# untitled.net
KiCad netlist of a schematic drawn in EAGLE
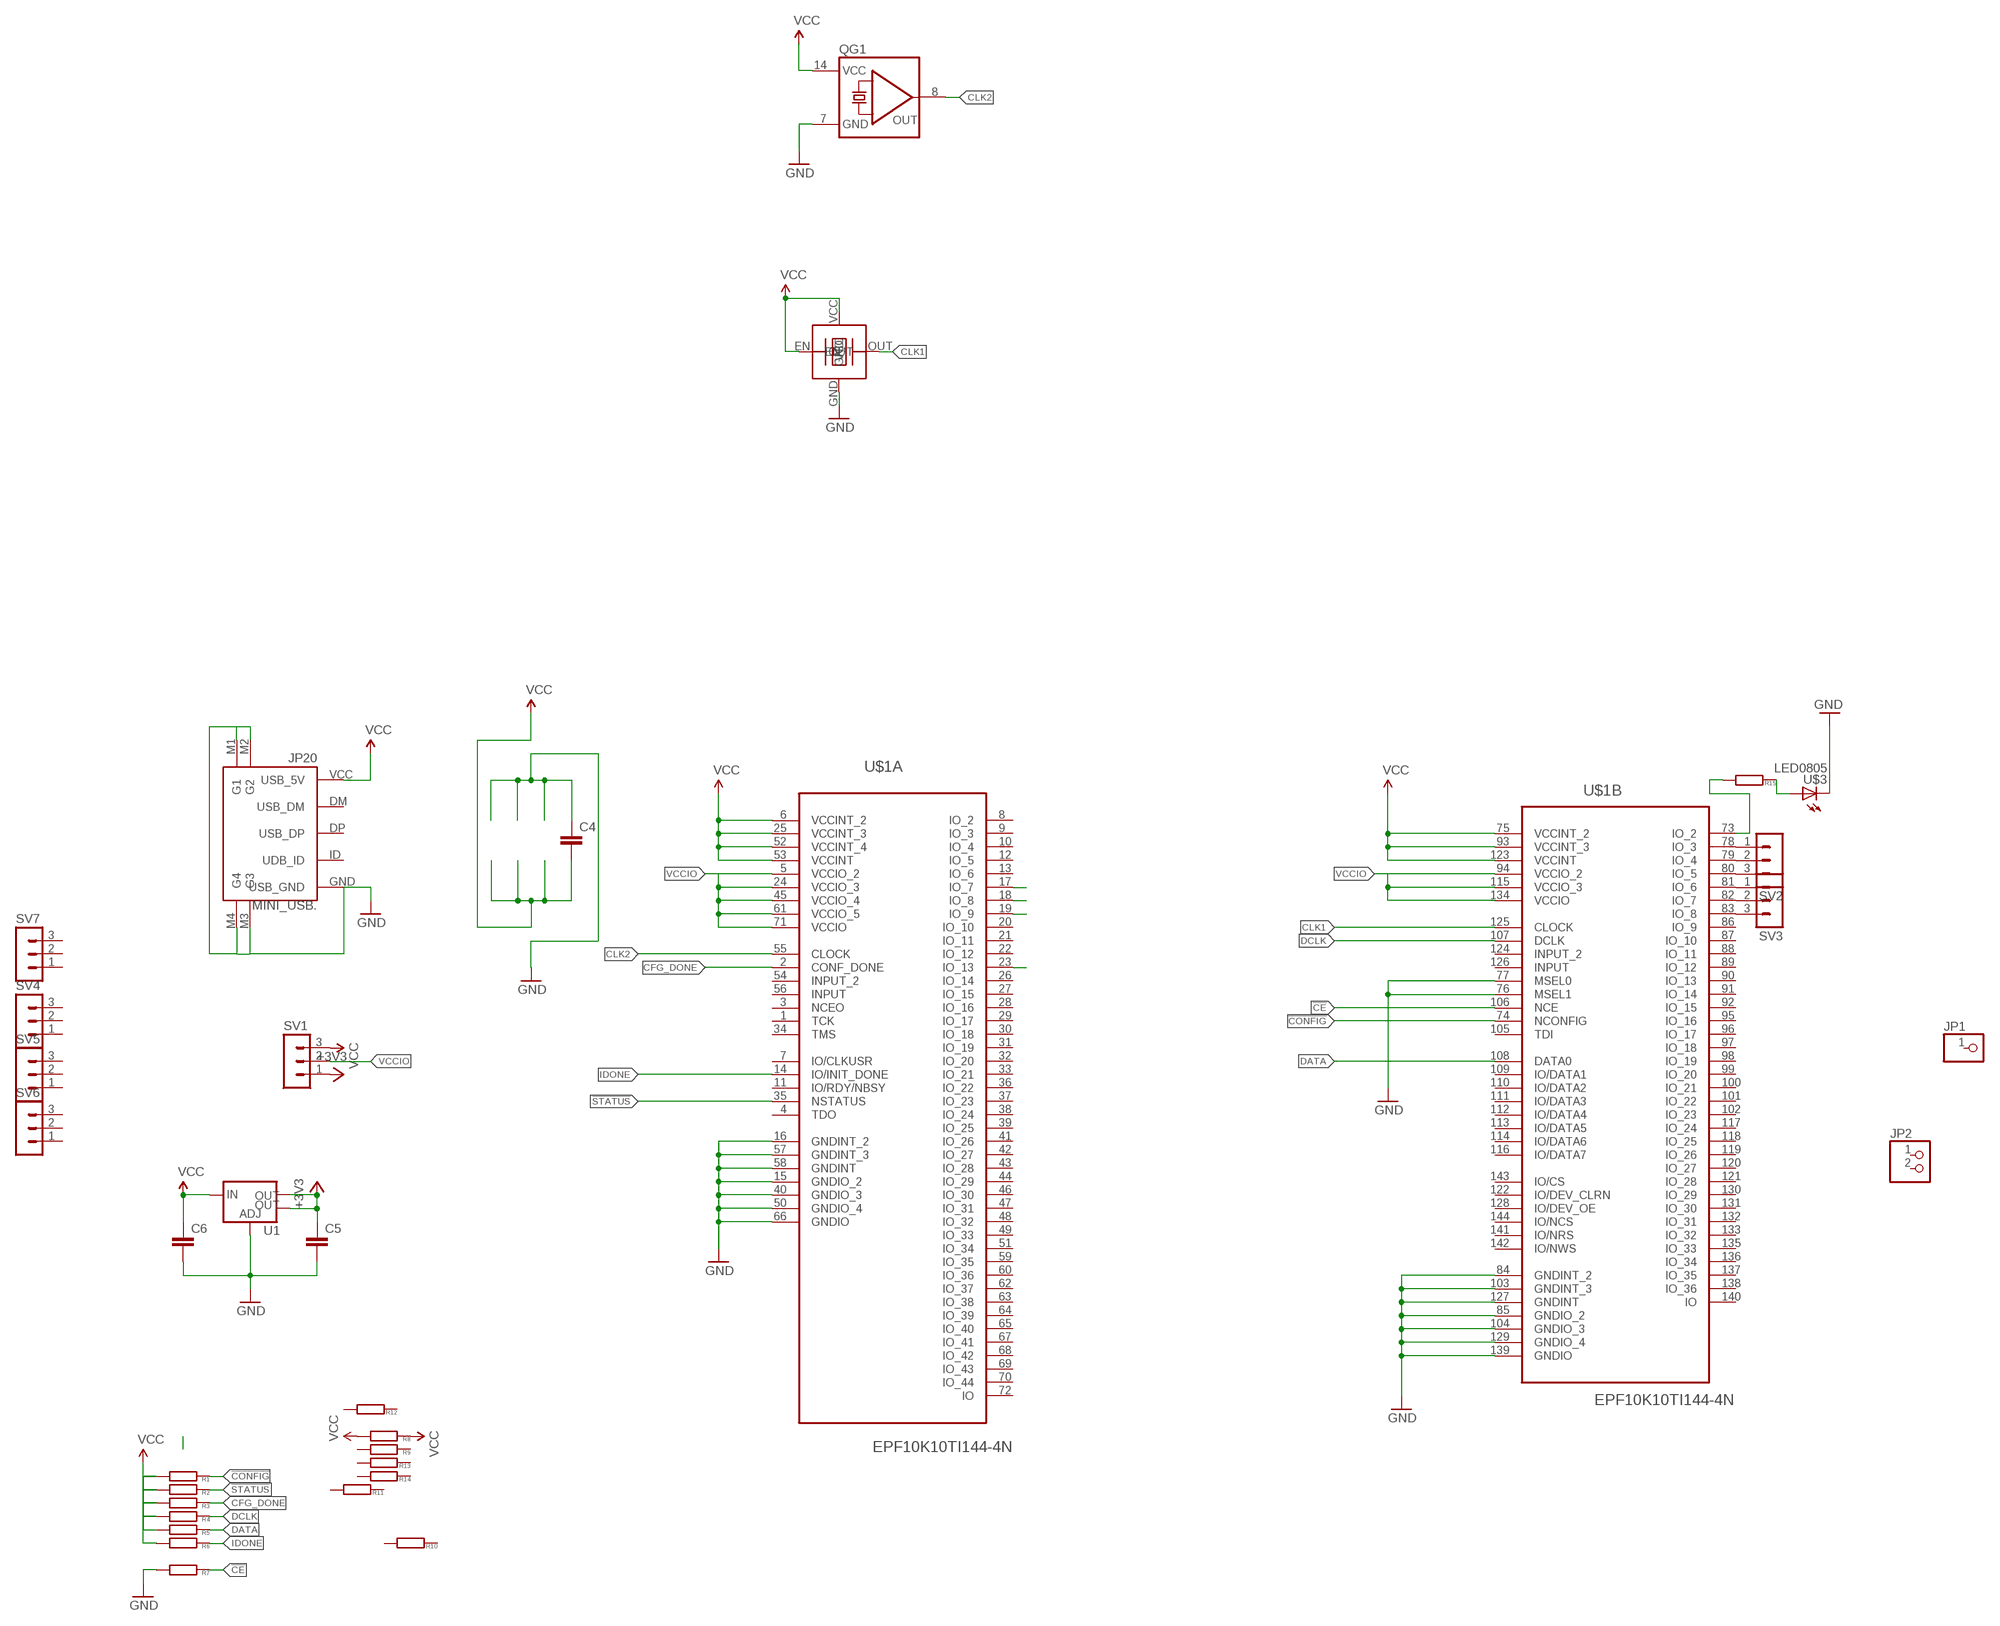
[diagram p0: schematic, sheet 1]

(export (version "E")
  (design (tool "Eeschema 10.0.6"))
  (components
    (comp (ref "C4")
      (value "CC0805")
      (footprint "eagle-import:C0805")
      (libsource (lib "eagle-import") (part "CC0805"))
    )
    (comp (ref "C5")
      (value "CC0805")
      (footprint "eagle-import:C0805")
      (libsource (lib "eagle-import") (part "CC0805"))
    )
    (comp (ref "C6")
      (value "CC0805")
      (footprint "eagle-import:C0805")
      (libsource (lib "eagle-import") (part "CC0805"))
    )
    (comp (ref "JP1")
      (value "PINHD-1X1")
      (footprint "eagle-import:1X01")
      (libsource (lib "eagle-import") (part "PINHD-1X1"))
    )
    (comp (ref "JP2")
      (value "PINHD-1X2")
      (footprint "eagle-import:1X02")
      (libsource (lib "eagle-import") (part "PINHD-1X2"))
    )
    (comp (ref "JP20")
      (value "MINI_USB.")
      (footprint "eagle-import:32005-201")
      (libsource (lib "eagle-import") (part "MINI_USB."))
    )
    (comp (ref "QG1")
      (value "QG5860")
      (footprint "eagle-import:DIL14S")
      (libsource (lib "eagle-import") (part "QG5860"))
    )
    (comp (ref "R1")
      (value "R0603")
      (footprint "eagle-import:0603")
      (libsource (lib "eagle-import") (part "R0603"))
    )
    (comp (ref "R2")
      (value "R0603")
      (footprint "eagle-import:0603")
      (libsource (lib "eagle-import") (part "R0603"))
    )
    (comp (ref "R3")
      (value "R0603")
      (footprint "eagle-import:0603")
      (libsource (lib "eagle-import") (part "R0603"))
    )
    (comp (ref "R4")
      (value "R0603")
      (footprint "eagle-import:0603")
      (libsource (lib "eagle-import") (part "R0603"))
    )
    (comp (ref "R5")
      (value "R0603")
      (footprint "eagle-import:0603")
      (libsource (lib "eagle-import") (part "R0603"))
    )
    (comp (ref "R6")
      (value "R0603")
      (footprint "eagle-import:0603")
      (libsource (lib "eagle-import") (part "R0603"))
    )
    (comp (ref "R7")
      (value "R0603")
      (footprint "eagle-import:0603")
      (libsource (lib "eagle-import") (part "R0603"))
    )
    (comp (ref "R8")
      (value "R0603")
      (footprint "eagle-import:0603")
      (libsource (lib "eagle-import") (part "R0603"))
    )
    (comp (ref "R9")
      (value "R0603")
      (footprint "eagle-import:0603")
      (libsource (lib "eagle-import") (part "R0603"))
    )
    (comp (ref "R10")
      (value "R0603")
      (footprint "eagle-import:0603")
      (libsource (lib "eagle-import") (part "R0603"))
    )
    (comp (ref "R11")
      (value "R0603")
      (footprint "eagle-import:0603")
      (libsource (lib "eagle-import") (part "R0603"))
    )
    (comp (ref "R12")
      (value "R0603")
      (footprint "eagle-import:0603")
      (libsource (lib "eagle-import") (part "R0603"))
    )
    (comp (ref "R13")
      (value "R0603")
      (footprint "eagle-import:0603")
      (libsource (lib "eagle-import") (part "R0603"))
    )
    (comp (ref "R14")
      (value "R0603")
      (footprint "eagle-import:0603")
      (libsource (lib "eagle-import") (part "R0603"))
    )
    (comp (ref "R15")
      (value "R0603")
      (footprint "eagle-import:0603")
      (libsource (lib "eagle-import") (part "R0603"))
    )
    (comp (ref "SV1")
      (value "MA03-1")
      (footprint "eagle-import:MA03-1")
      (libsource (lib "eagle-import") (part "MA03-1"))
    )
    (comp (ref "SV2")
      (value "MA03-1")
      (footprint "eagle-import:MA03-1")
      (libsource (lib "eagle-import") (part "MA03-1"))
    )
    (comp (ref "SV3")
      (value "MA03-1")
      (footprint "eagle-import:MA03-1")
      (libsource (lib "eagle-import") (part "MA03-1"))
    )
    (comp (ref "SV4")
      (value "MA03-1")
      (footprint "eagle-import:MA03-1")
      (libsource (lib "eagle-import") (part "MA03-1"))
    )
    (comp (ref "SV5")
      (value "MA03-1")
      (footprint "eagle-import:MA03-1")
      (libsource (lib "eagle-import") (part "MA03-1"))
    )
    (comp (ref "SV6")
      (value "MA03-1")
      (footprint "eagle-import:MA03-1")
      (libsource (lib "eagle-import") (part "MA03-1"))
    )
    (comp (ref "SV7")
      (value "MA03-1")
      (footprint "eagle-import:MA03-1")
      (libsource (lib "eagle-import") (part "MA03-1"))
    )
    (comp (ref "U$1")
      (value "EPF10K10TI144-4N")
      (footprint "eagle-import:QFP50P2200X2200X160-144N")
      (libsource (lib "eagle-import") (part "EPF10K10TI144-4N"))
    )
    (comp (ref "U$2")
      (value "TXC-BA")
      (footprint "eagle-import:7X5")
      (libsource (lib "eagle-import") (part "TXC-BA"))
    )
    (comp (ref "U$3")
      (value "LED0805")
      (footprint "eagle-import:0805-LED")
      (libsource (lib "eagle-import") (part "LED0805"))
    )
    (comp (ref "U1")
      (value "V_REG_LM1117SOT223")
      (footprint "eagle-import:SOT223")
      (libsource (lib "eagle-import") (part "V_REG_LM1117SOT223"))
    )
  )
  (nets
    (net (code "1") (name "+3V3") (class "Default")
      (node (ref "C5") (pin "1") (pinfunction "1_1") (pintype "passive"))
      (node (ref "SV1") (pin "1") (pinfunction "1_1") (pintype "passive"))
      (node (ref "U1") (pin "2") (pinfunction "OUT_2") (pintype "output"))
      (node (ref "U1") (pin "4") (pinfunction "OUT_4") (pintype "output"))
    )
    (net (code "2") (name "/~{CE}") (class "Default")
      (node (ref "R7") (pin "1") (pinfunction "1_1") (pintype "passive"))
      (node (ref "U$1") (pin "106") (pinfunction "NCE_106") (pintype "input"))
    )
    (net (code "3") (name "/~{CONFIG}") (class "Default")
      (node (ref "R1") (pin "1") (pinfunction "1_1") (pintype "passive"))
      (node (ref "U$1") (pin "74") (pinfunction "NCONFIG_74") (pintype "input"))
    )
    (net (code "4") (name "/~{STATUS}") (class "Default")
      (node (ref "R2") (pin "1") (pinfunction "1_1") (pintype "passive"))
      (node (ref "U$1") (pin "35") (pinfunction "NSTATUS_35") (pintype "output"))
    )
    (net (code "5") (name "CFG_DONE") (class "Default")
      (node (ref "R3") (pin "1") (pinfunction "1_1") (pintype "passive"))
      (node (ref "U$1") (pin "2") (pinfunction "CONF_DONE_2") (pintype "input"))
    )
    (net (code "6") (name "CLK1") (class "Default")
      (node (ref "U$1") (pin "125") (pinfunction "CLOCK_125") (pintype "input"))
      (node (ref "U$2") (pin "OUT") (pinfunction "OUT_OUT") (pintype "bidirectional"))
    )
    (net (code "7") (name "CLK2") (class "Default")
      (node (ref "QG1") (pin "8") (pinfunction "OUT_8") (pintype "output"))
      (node (ref "U$1") (pin "55") (pinfunction "CLOCK_55") (pintype "input"))
    )
    (net (code "8") (name "DATA") (class "Default")
      (node (ref "R5") (pin "1") (pinfunction "1_1") (pintype "passive"))
      (node (ref "U$1") (pin "108") (pinfunction "DATA0_108") (pintype "bidirectional"))
    )
    (net (code "9") (name "DCLK") (class "Default")
      (node (ref "R4") (pin "1") (pinfunction "1_1") (pintype "passive"))
      (node (ref "U$1") (pin "107") (pinfunction "DCLK_107") (pintype "input"))
    )
    (net (code "10") (name "GND") (class "Default")
      (node (ref "C4") (pin "1") (pinfunction "1_1") (pintype "passive"))
      (node (ref "C5") (pin "2") (pinfunction "2_2") (pintype "passive"))
      (node (ref "C6") (pin "2") (pinfunction "2_2") (pintype "passive"))
      (node (ref "JP20") (pin "GND") (pinfunction "USB_GND_GND") (pintype "power_in"))
      (node (ref "JP20") (pin "M1") (pinfunction "G1_M1") (pintype "bidirectional"))
      (node (ref "JP20") (pin "M2") (pinfunction "G2_M2") (pintype "bidirectional"))
      (node (ref "JP20") (pin "M3") (pinfunction "G3_M3") (pintype "bidirectional"))
      (node (ref "JP20") (pin "M4") (pinfunction "G4_M4") (pintype "bidirectional"))
      (node (ref "QG1") (pin "7") (pinfunction "GND_7") (pintype "power_in"))
      (node (ref "R7") (pin "2") (pinfunction "2_2") (pintype "passive"))
      (node (ref "U$1") (pin "103") (pinfunction "GNDINT_3_103") (pintype "passive"))
      (node (ref "U$1") (pin "104") (pinfunction "GNDIO_3_104") (pintype "passive"))
      (node (ref "U$1") (pin "127") (pinfunction "GNDINT_127") (pintype "passive"))
      (node (ref "U$1") (pin "129") (pinfunction "GNDIO_4_129") (pintype "passive"))
      (node (ref "U$1") (pin "139") (pinfunction "GNDIO_139") (pintype "passive"))
      (node (ref "U$1") (pin "15") (pinfunction "GNDIO_2_15") (pintype "passive"))
      (node (ref "U$1") (pin "16") (pinfunction "GNDINT_2_16") (pintype "passive"))
      (node (ref "U$1") (pin "40") (pinfunction "GNDIO_3_40") (pintype "passive"))
      (node (ref "U$1") (pin "50") (pinfunction "GNDIO_4_50") (pintype "passive"))
      (node (ref "U$1") (pin "57") (pinfunction "GNDINT_3_57") (pintype "passive"))
      (node (ref "U$1") (pin "58") (pinfunction "GNDINT_58") (pintype "passive"))
      (node (ref "U$1") (pin "66") (pinfunction "GNDIO_66") (pintype "passive"))
      (node (ref "U$1") (pin "76") (pinfunction "MSEL1_76") (pintype "input"))
      (node (ref "U$1") (pin "77") (pinfunction "MSEL0_77") (pintype "input"))
      (node (ref "U$1") (pin "84") (pinfunction "GNDINT_2_84") (pintype "passive"))
      (node (ref "U$1") (pin "85") (pinfunction "GNDIO_2_85") (pintype "passive"))
      (node (ref "U$2") (pin "GND") (pinfunction "GND_GND") (pintype "bidirectional"))
      (node (ref "U$3") (pin "C") (pinfunction "C_C") (pintype "passive"))
      (node (ref "U1") (pin "1") (pinfunction "ADJ_1") (pintype "input"))
    )
    (net (code "11") (name "IDONE") (class "Default")
      (node (ref "R6") (pin "1") (pinfunction "1_1") (pintype "passive"))
      (node (ref "U$1") (pin "14") (pinfunction "IO/INIT_DONE_14") (pintype "bidirectional"))
    )
    (net (code "12") (name "Net-(R15-Pad1)") (class "Default")
      (node (ref "R15") (pin "1") (pinfunction "1_1") (pintype "passive"))
      (node (ref "U$3") (pin "A") (pinfunction "A_A") (pintype "passive"))
    )
    (net (code "13") (name "Net-(U$1B-IO_2)") (class "Default")
      (node (ref "R15") (pin "2") (pinfunction "2_2") (pintype "passive"))
      (node (ref "U$1") (pin "73") (pinfunction "IO_2_73") (pintype "bidirectional"))
    )
    (net (code "14") (name "Net-(U$1B-IO_3)") (class "Default")
      (node (ref "SV2") (pin "1") (pinfunction "1_1") (pintype "passive"))
      (node (ref "U$1") (pin "78") (pinfunction "IO_3_78") (pintype "bidirectional"))
    )
    (net (code "15") (name "Net-(U$1B-IO_4)") (class "Default")
      (node (ref "SV2") (pin "2") (pinfunction "2_2") (pintype "passive"))
      (node (ref "U$1") (pin "79") (pinfunction "IO_4_79") (pintype "bidirectional"))
    )
    (net (code "16") (name "Net-(U$1B-IO_5)") (class "Default")
      (node (ref "SV2") (pin "3") (pinfunction "3_3") (pintype "passive"))
      (node (ref "U$1") (pin "80") (pinfunction "IO_5_80") (pintype "bidirectional"))
    )
    (net (code "17") (name "Net-(U$1B-IO_6)") (class "Default")
      (node (ref "SV3") (pin "1") (pinfunction "1_1") (pintype "passive"))
      (node (ref "U$1") (pin "81") (pinfunction "IO_6_81") (pintype "bidirectional"))
    )
    (net (code "18") (name "Net-(U$1B-IO_7)") (class "Default")
      (node (ref "SV3") (pin "2") (pinfunction "2_2") (pintype "passive"))
      (node (ref "U$1") (pin "82") (pinfunction "IO_7_82") (pintype "bidirectional"))
    )
    (net (code "19") (name "Net-(U$1B-IO_8)") (class "Default")
      (node (ref "SV3") (pin "3") (pinfunction "3_3") (pintype "passive"))
      (node (ref "U$1") (pin "83") (pinfunction "IO_8_83") (pintype "bidirectional"))
    )
    (net (code "20") (name "VCC") (class "Default")
      (node (ref "C4") (pin "2") (pinfunction "2_2") (pintype "passive"))
      (node (ref "C6") (pin "1") (pinfunction "1_1") (pintype "passive"))
      (node (ref "JP20") (pin "VCC") (pinfunction "USB_5V_VCC") (pintype "power_in"))
      (node (ref "QG1") (pin "14") (pinfunction "VCC_14") (pintype "power_in"))
      (node (ref "R1") (pin "2") (pinfunction "2_2") (pintype "passive"))
      (node (ref "R2") (pin "2") (pinfunction "2_2") (pintype "passive"))
      (node (ref "R3") (pin "2") (pinfunction "2_2") (pintype "passive"))
      (node (ref "R4") (pin "2") (pinfunction "2_2") (pintype "passive"))
      (node (ref "R5") (pin "2") (pinfunction "2_2") (pintype "passive"))
      (node (ref "R6") (pin "2") (pinfunction "2_2") (pintype "passive"))
      (node (ref "R8") (pin "1") (pinfunction "1_1") (pintype "passive"))
      (node (ref "R8") (pin "2") (pinfunction "2_2") (pintype "passive"))
      (node (ref "SV1") (pin "3") (pinfunction "3_3") (pintype "passive"))
      (node (ref "U$1") (pin "123") (pinfunction "VCCINT_123") (pintype "power_in"))
      (node (ref "U$1") (pin "25") (pinfunction "VCCINT_3_25") (pintype "power_in"))
      (node (ref "U$1") (pin "52") (pinfunction "VCCINT_4_52") (pintype "power_in"))
      (node (ref "U$1") (pin "53") (pinfunction "VCCINT_53") (pintype "power_in"))
      (node (ref "U$1") (pin "6") (pinfunction "VCCINT_2_6") (pintype "power_in"))
      (node (ref "U$1") (pin "75") (pinfunction "VCCINT_2_75") (pintype "power_in"))
      (node (ref "U$1") (pin "93") (pinfunction "VCCINT_3_93") (pintype "power_in"))
      (node (ref "U$2") (pin "EN") (pinfunction "EN_EN") (pintype "bidirectional"))
      (node (ref "U$2") (pin "VCC") (pinfunction "VCC_VCC") (pintype "bidirectional"))
      (node (ref "U1") (pin "3") (pinfunction "IN_3") (pintype "input"))
    )
    (net (code "21") (name "VCCIO") (class "Default")
      (node (ref "SV1") (pin "2") (pinfunction "2_2") (pintype "passive"))
      (node (ref "U$1") (pin "115") (pinfunction "VCCIO_3_115") (pintype "power_in"))
      (node (ref "U$1") (pin "134") (pinfunction "VCCIO_134") (pintype "power_in"))
      (node (ref "U$1") (pin "24") (pinfunction "VCCIO_3_24") (pintype "power_in"))
      (node (ref "U$1") (pin "45") (pinfunction "VCCIO_4_45") (pintype "power_in"))
      (node (ref "U$1") (pin "5") (pinfunction "VCCIO_2_5") (pintype "power_in"))
      (node (ref "U$1") (pin "61") (pinfunction "VCCIO_5_61") (pintype "power_in"))
      (node (ref "U$1") (pin "71") (pinfunction "VCCIO_71") (pintype "power_in"))
      (node (ref "U$1") (pin "94") (pinfunction "VCCIO_2_94") (pintype "power_in"))
    )
    (net (code "22") (name "unconnected-(JP1-Pad1)") (class "Default")
      (node (ref "JP1") (pin "1") (pinfunction "1_1") (pintype "passive"))
    )
    (net (code "23") (name "unconnected-(JP2-Pad1)") (class "Default")
      (node (ref "JP2") (pin "1") (pinfunction "1_1") (pintype "passive"))
    )
    (net (code "24") (name "unconnected-(JP2-Pad2)") (class "Default")
      (node (ref "JP2") (pin "2") (pinfunction "2_2") (pintype "passive"))
    )
    (net (code "25") (name "unconnected-(JP20-UDB_ID-PadID)") (class "Default")
      (node (ref "JP20") (pin "ID") (pinfunction "UDB_ID_ID") (pintype "bidirectional"))
    )
    (net (code "26") (name "unconnected-(JP20-USB_DM-PadDM)") (class "Default")
      (node (ref "JP20") (pin "DM") (pinfunction "USB_DM_DM") (pintype "bidirectional"))
    )
    (net (code "27") (name "unconnected-(JP20-USB_DP-PadDP)") (class "Default")
      (node (ref "JP20") (pin "DP") (pinfunction "USB_DP_DP") (pintype "bidirectional"))
    )
    (net (code "28") (name "unconnected-(R9-Pad1)") (class "Default")
      (node (ref "R9") (pin "1") (pinfunction "1_1") (pintype "passive"))
    )
    (net (code "29") (name "unconnected-(R9-Pad2)") (class "Default")
      (node (ref "R9") (pin "2") (pinfunction "2_2") (pintype "passive"))
    )
    (net (code "30") (name "unconnected-(R10-Pad1)") (class "Default")
      (node (ref "R10") (pin "1") (pinfunction "1_1") (pintype "passive"))
    )
    (net (code "31") (name "unconnected-(R10-Pad2)") (class "Default")
      (node (ref "R10") (pin "2") (pinfunction "2_2") (pintype "passive"))
    )
    (net (code "32") (name "unconnected-(R11-Pad1)") (class "Default")
      (node (ref "R11") (pin "1") (pinfunction "1_1") (pintype "passive"))
    )
    (net (code "33") (name "unconnected-(R11-Pad2)") (class "Default")
      (node (ref "R11") (pin "2") (pinfunction "2_2") (pintype "passive"))
    )
    (net (code "34") (name "unconnected-(R12-Pad1)") (class "Default")
      (node (ref "R12") (pin "1") (pinfunction "1_1") (pintype "passive"))
    )
    (net (code "35") (name "unconnected-(R12-Pad2)") (class "Default")
      (node (ref "R12") (pin "2") (pinfunction "2_2") (pintype "passive"))
    )
    (net (code "36") (name "unconnected-(R13-Pad1)") (class "Default")
      (node (ref "R13") (pin "1") (pinfunction "1_1") (pintype "passive"))
    )
    (net (code "37") (name "unconnected-(R13-Pad2)") (class "Default")
      (node (ref "R13") (pin "2") (pinfunction "2_2") (pintype "passive"))
    )
    (net (code "38") (name "unconnected-(R14-Pad1)") (class "Default")
      (node (ref "R14") (pin "1") (pinfunction "1_1") (pintype "passive"))
    )
    (net (code "39") (name "unconnected-(R14-Pad2)") (class "Default")
      (node (ref "R14") (pin "2") (pinfunction "2_2") (pintype "passive"))
    )
    (net (code "40") (name "unconnected-(SV4-Pad1)") (class "Default")
      (node (ref "SV4") (pin "1") (pinfunction "1_1") (pintype "passive"))
    )
    (net (code "41") (name "unconnected-(SV4-Pad2)") (class "Default")
      (node (ref "SV4") (pin "2") (pinfunction "2_2") (pintype "passive"))
    )
    (net (code "42") (name "unconnected-(SV4-Pad3)") (class "Default")
      (node (ref "SV4") (pin "3") (pinfunction "3_3") (pintype "passive"))
    )
    (net (code "43") (name "unconnected-(SV5-Pad1)") (class "Default")
      (node (ref "SV5") (pin "1") (pinfunction "1_1") (pintype "passive"))
    )
    (net (code "44") (name "unconnected-(SV5-Pad2)") (class "Default")
      (node (ref "SV5") (pin "2") (pinfunction "2_2") (pintype "passive"))
    )
    (net (code "45") (name "unconnected-(SV5-Pad3)") (class "Default")
      (node (ref "SV5") (pin "3") (pinfunction "3_3") (pintype "passive"))
    )
    (net (code "46") (name "unconnected-(SV6-Pad1)") (class "Default")
      (node (ref "SV6") (pin "1") (pinfunction "1_1") (pintype "passive"))
    )
    (net (code "47") (name "unconnected-(SV6-Pad2)") (class "Default")
      (node (ref "SV6") (pin "2") (pinfunction "2_2") (pintype "passive"))
    )
    (net (code "48") (name "unconnected-(SV6-Pad3)") (class "Default")
      (node (ref "SV6") (pin "3") (pinfunction "3_3") (pintype "passive"))
    )
    (net (code "49") (name "unconnected-(SV7-Pad1)") (class "Default")
      (node (ref "SV7") (pin "1") (pinfunction "1_1") (pintype "passive"))
    )
    (net (code "50") (name "unconnected-(SV7-Pad2)") (class "Default")
      (node (ref "SV7") (pin "2") (pinfunction "2_2") (pintype "passive"))
    )
    (net (code "51") (name "unconnected-(SV7-Pad3)") (class "Default")
      (node (ref "SV7") (pin "3") (pinfunction "3_3") (pintype "passive"))
    )
    (net (code "52") (name "unconnected-(U$1A-INPUT-Pad56)") (class "Default")
      (node (ref "U$1") (pin "56") (pinfunction "INPUT_56") (pintype "input"))
    )
    (net (code "53") (name "unconnected-(U$1A-INPUT_2-Pad54)") (class "Default")
      (node (ref "U$1") (pin "54") (pinfunction "INPUT_2_54") (pintype "input"))
    )
    (net (code "54") (name "unconnected-(U$1A-IO-Pad72)") (class "Default")
      (node (ref "U$1") (pin "72") (pinfunction "IO_72") (pintype "bidirectional"))
    )
    (net (code "55") (name "unconnected-(U$1A-IO_2-Pad8)") (class "Default")
      (node (ref "U$1") (pin "8") (pinfunction "IO_2_8") (pintype "bidirectional"))
    )
    (net (code "56") (name "unconnected-(U$1A-IO_3-Pad9)") (class "Default")
      (node (ref "U$1") (pin "9") (pinfunction "IO_3_9") (pintype "bidirectional"))
    )
    (net (code "57") (name "unconnected-(U$1A-IO_4-Pad10)") (class "Default")
      (node (ref "U$1") (pin "10") (pinfunction "IO_4_10") (pintype "bidirectional"))
    )
    (net (code "58") (name "unconnected-(U$1A-IO_5-Pad12)") (class "Default")
      (node (ref "U$1") (pin "12") (pinfunction "IO_5_12") (pintype "bidirectional"))
    )
    (net (code "59") (name "unconnected-(U$1A-IO_6-Pad13)") (class "Default")
      (node (ref "U$1") (pin "13") (pinfunction "IO_6_13") (pintype "bidirectional"))
    )
    (net (code "60") (name "unconnected-(U$1A-IO_7-Pad17)") (class "Default")
      (node (ref "U$1") (pin "17") (pinfunction "IO_7_17") (pintype "bidirectional"))
    )
    (net (code "61") (name "unconnected-(U$1A-IO_8-Pad18)") (class "Default")
      (node (ref "U$1") (pin "18") (pinfunction "IO_8_18") (pintype "bidirectional"))
    )
    (net (code "62") (name "unconnected-(U$1A-IO_9-Pad19)") (class "Default")
      (node (ref "U$1") (pin "19") (pinfunction "IO_9_19") (pintype "bidirectional"))
    )
    (net (code "63") (name "unconnected-(U$1A-IO_10-Pad20)") (class "Default")
      (node (ref "U$1") (pin "20") (pinfunction "IO_10_20") (pintype "bidirectional"))
    )
    (net (code "64") (name "unconnected-(U$1A-IO_11-Pad21)") (class "Default")
      (node (ref "U$1") (pin "21") (pinfunction "IO_11_21") (pintype "bidirectional"))
    )
    (net (code "65") (name "unconnected-(U$1A-IO_12-Pad22)") (class "Default")
      (node (ref "U$1") (pin "22") (pinfunction "IO_12_22") (pintype "bidirectional"))
    )
    (net (code "66") (name "unconnected-(U$1A-IO_13-Pad23)") (class "Default")
      (node (ref "U$1") (pin "23") (pinfunction "IO_13_23") (pintype "bidirectional"))
    )
    (net (code "67") (name "unconnected-(U$1A-IO_14-Pad26)") (class "Default")
      (node (ref "U$1") (pin "26") (pinfunction "IO_14_26") (pintype "bidirectional"))
    )
    (net (code "68") (name "unconnected-(U$1A-IO_15-Pad27)") (class "Default")
      (node (ref "U$1") (pin "27") (pinfunction "IO_15_27") (pintype "bidirectional"))
    )
    (net (code "69") (name "unconnected-(U$1A-IO_16-Pad28)") (class "Default")
      (node (ref "U$1") (pin "28") (pinfunction "IO_16_28") (pintype "bidirectional"))
    )
    (net (code "70") (name "unconnected-(U$1A-IO_17-Pad29)") (class "Default")
      (node (ref "U$1") (pin "29") (pinfunction "IO_17_29") (pintype "bidirectional"))
    )
    (net (code "71") (name "unconnected-(U$1A-IO_18-Pad30)") (class "Default")
      (node (ref "U$1") (pin "30") (pinfunction "IO_18_30") (pintype "bidirectional"))
    )
    (net (code "72") (name "unconnected-(U$1A-IO_19-Pad31)") (class "Default")
      (node (ref "U$1") (pin "31") (pinfunction "IO_19_31") (pintype "bidirectional"))
    )
    (net (code "73") (name "unconnected-(U$1A-IO_20-Pad32)") (class "Default")
      (node (ref "U$1") (pin "32") (pinfunction "IO_20_32") (pintype "bidirectional"))
    )
    (net (code "74") (name "unconnected-(U$1A-IO_21-Pad33)") (class "Default")
      (node (ref "U$1") (pin "33") (pinfunction "IO_21_33") (pintype "bidirectional"))
    )
    (net (code "75") (name "unconnected-(U$1A-IO_22-Pad36)") (class "Default")
      (node (ref "U$1") (pin "36") (pinfunction "IO_22_36") (pintype "bidirectional"))
    )
    (net (code "76") (name "unconnected-(U$1A-IO_23-Pad37)") (class "Default")
      (node (ref "U$1") (pin "37") (pinfunction "IO_23_37") (pintype "bidirectional"))
    )
    (net (code "77") (name "unconnected-(U$1A-IO_24-Pad38)") (class "Default")
      (node (ref "U$1") (pin "38") (pinfunction "IO_24_38") (pintype "bidirectional"))
    )
    (net (code "78") (name "unconnected-(U$1A-IO_25-Pad39)") (class "Default")
      (node (ref "U$1") (pin "39") (pinfunction "IO_25_39") (pintype "bidirectional"))
    )
    (net (code "79") (name "unconnected-(U$1A-IO_26-Pad41)") (class "Default")
      (node (ref "U$1") (pin "41") (pinfunction "IO_26_41") (pintype "bidirectional"))
    )
    (net (code "80") (name "unconnected-(U$1A-IO_27-Pad42)") (class "Default")
      (node (ref "U$1") (pin "42") (pinfunction "IO_27_42") (pintype "bidirectional"))
    )
    (net (code "81") (name "unconnected-(U$1A-IO_28-Pad43)") (class "Default")
      (node (ref "U$1") (pin "43") (pinfunction "IO_28_43") (pintype "bidirectional"))
    )
    (net (code "82") (name "unconnected-(U$1A-IO_29-Pad44)") (class "Default")
      (node (ref "U$1") (pin "44") (pinfunction "IO_29_44") (pintype "bidirectional"))
    )
    (net (code "83") (name "unconnected-(U$1A-IO_30-Pad46)") (class "Default")
      (node (ref "U$1") (pin "46") (pinfunction "IO_30_46") (pintype "bidirectional"))
    )
    (net (code "84") (name "unconnected-(U$1A-IO_31-Pad47)") (class "Default")
      (node (ref "U$1") (pin "47") (pinfunction "IO_31_47") (pintype "bidirectional"))
    )
    (net (code "85") (name "unconnected-(U$1A-IO_32-Pad48)") (class "Default")
      (node (ref "U$1") (pin "48") (pinfunction "IO_32_48") (pintype "bidirectional"))
    )
    (net (code "86") (name "unconnected-(U$1A-IO_33-Pad49)") (class "Default")
      (node (ref "U$1") (pin "49") (pinfunction "IO_33_49") (pintype "bidirectional"))
    )
    (net (code "87") (name "unconnected-(U$1A-IO_34-Pad51)") (class "Default")
      (node (ref "U$1") (pin "51") (pinfunction "IO_34_51") (pintype "bidirectional"))
    )
    (net (code "88") (name "unconnected-(U$1A-IO_35-Pad59)") (class "Default")
      (node (ref "U$1") (pin "59") (pinfunction "IO_35_59") (pintype "bidirectional"))
    )
    (net (code "89") (name "unconnected-(U$1A-IO_36-Pad60)") (class "Default")
      (node (ref "U$1") (pin "60") (pinfunction "IO_36_60") (pintype "bidirectional"))
    )
    (net (code "90") (name "unconnected-(U$1A-IO_37-Pad62)") (class "Default")
      (node (ref "U$1") (pin "62") (pinfunction "IO_37_62") (pintype "bidirectional"))
    )
    (net (code "91") (name "unconnected-(U$1A-IO_38-Pad63)") (class "Default")
      (node (ref "U$1") (pin "63") (pinfunction "IO_38_63") (pintype "bidirectional"))
    )
    (net (code "92") (name "unconnected-(U$1A-IO_39-Pad64)") (class "Default")
      (node (ref "U$1") (pin "64") (pinfunction "IO_39_64") (pintype "bidirectional"))
    )
    (net (code "93") (name "unconnected-(U$1A-IO_40-Pad65)") (class "Default")
      (node (ref "U$1") (pin "65") (pinfunction "IO_40_65") (pintype "bidirectional"))
    )
    (net (code "94") (name "unconnected-(U$1A-IO_41-Pad67)") (class "Default")
      (node (ref "U$1") (pin "67") (pinfunction "IO_41_67") (pintype "bidirectional"))
    )
    (net (code "95") (name "unconnected-(U$1A-IO_42-Pad68)") (class "Default")
      (node (ref "U$1") (pin "68") (pinfunction "IO_42_68") (pintype "bidirectional"))
    )
    (net (code "96") (name "unconnected-(U$1A-IO_43-Pad69)") (class "Default")
      (node (ref "U$1") (pin "69") (pinfunction "IO_43_69") (pintype "bidirectional"))
    )
    (net (code "97") (name "unconnected-(U$1A-IO_44-Pad70)") (class "Default")
      (node (ref "U$1") (pin "70") (pinfunction "IO_44_70") (pintype "bidirectional"))
    )
    (net (code "98") (name "unconnected-(U$1A-IO{slash}CLKUSR-Pad7)") (class "Default")
      (node (ref "U$1") (pin "7") (pinfunction "IO/CLKUSR_7") (pintype "bidirectional"))
    )
    (net (code "99") (name "unconnected-(U$1A-IO{slash}RDY{slash}NBSY-Pad11)") (class "Default")
      (node (ref "U$1") (pin "11") (pinfunction "IO/RDY/NBSY_11") (pintype "bidirectional"))
    )
    (net (code "100") (name "unconnected-(U$1A-NCEO-Pad3)") (class "Default")
      (node (ref "U$1") (pin "3") (pinfunction "NCEO_3") (pintype "input"))
    )
    (net (code "101") (name "unconnected-(U$1A-TCK-Pad1)") (class "Default")
      (node (ref "U$1") (pin "1") (pinfunction "TCK_1") (pintype "input"))
    )
    (net (code "102") (name "unconnected-(U$1A-TDO-Pad4)") (class "Default")
      (node (ref "U$1") (pin "4") (pinfunction "TDO_4") (pintype "output"))
    )
    (net (code "103") (name "unconnected-(U$1A-TMS-Pad34)") (class "Default")
      (node (ref "U$1") (pin "34") (pinfunction "TMS_34") (pintype "input"))
    )
    (net (code "104") (name "unconnected-(U$1B-INPUT-Pad126)") (class "Default")
      (node (ref "U$1") (pin "126") (pinfunction "INPUT_126") (pintype "input"))
    )
    (net (code "105") (name "unconnected-(U$1B-INPUT_2-Pad124)") (class "Default")
      (node (ref "U$1") (pin "124") (pinfunction "INPUT_2_124") (pintype "input"))
    )
    (net (code "106") (name "unconnected-(U$1B-IO-Pad140)") (class "Default")
      (node (ref "U$1") (pin "140") (pinfunction "IO_140") (pintype "bidirectional"))
    )
    (net (code "107") (name "unconnected-(U$1B-IO_9-Pad86)") (class "Default")
      (node (ref "U$1") (pin "86") (pinfunction "IO_9_86") (pintype "bidirectional"))
    )
    (net (code "108") (name "unconnected-(U$1B-IO_10-Pad87)") (class "Default")
      (node (ref "U$1") (pin "87") (pinfunction "IO_10_87") (pintype "bidirectional"))
    )
    (net (code "109") (name "unconnected-(U$1B-IO_11-Pad88)") (class "Default")
      (node (ref "U$1") (pin "88") (pinfunction "IO_11_88") (pintype "bidirectional"))
    )
    (net (code "110") (name "unconnected-(U$1B-IO_12-Pad89)") (class "Default")
      (node (ref "U$1") (pin "89") (pinfunction "IO_12_89") (pintype "bidirectional"))
    )
    (net (code "111") (name "unconnected-(U$1B-IO_13-Pad90)") (class "Default")
      (node (ref "U$1") (pin "90") (pinfunction "IO_13_90") (pintype "bidirectional"))
    )
    (net (code "112") (name "unconnected-(U$1B-IO_14-Pad91)") (class "Default")
      (node (ref "U$1") (pin "91") (pinfunction "IO_14_91") (pintype "bidirectional"))
    )
    (net (code "113") (name "unconnected-(U$1B-IO_15-Pad92)") (class "Default")
      (node (ref "U$1") (pin "92") (pinfunction "IO_15_92") (pintype "bidirectional"))
    )
    (net (code "114") (name "unconnected-(U$1B-IO_16-Pad95)") (class "Default")
      (node (ref "U$1") (pin "95") (pinfunction "IO_16_95") (pintype "bidirectional"))
    )
    (net (code "115") (name "unconnected-(U$1B-IO_17-Pad96)") (class "Default")
      (node (ref "U$1") (pin "96") (pinfunction "IO_17_96") (pintype "bidirectional"))
    )
    (net (code "116") (name "unconnected-(U$1B-IO_18-Pad97)") (class "Default")
      (node (ref "U$1") (pin "97") (pinfunction "IO_18_97") (pintype "bidirectional"))
    )
    (net (code "117") (name "unconnected-(U$1B-IO_19-Pad98)") (class "Default")
      (node (ref "U$1") (pin "98") (pinfunction "IO_19_98") (pintype "bidirectional"))
    )
    (net (code "118") (name "unconnected-(U$1B-IO_20-Pad99)") (class "Default")
      (node (ref "U$1") (pin "99") (pinfunction "IO_20_99") (pintype "bidirectional"))
    )
    (net (code "119") (name "unconnected-(U$1B-IO_21-Pad100)") (class "Default")
      (node (ref "U$1") (pin "100") (pinfunction "IO_21_100") (pintype "bidirectional"))
    )
    (net (code "120") (name "unconnected-(U$1B-IO_22-Pad101)") (class "Default")
      (node (ref "U$1") (pin "101") (pinfunction "IO_22_101") (pintype "bidirectional"))
    )
    (net (code "121") (name "unconnected-(U$1B-IO_23-Pad102)") (class "Default")
      (node (ref "U$1") (pin "102") (pinfunction "IO_23_102") (pintype "bidirectional"))
    )
    (net (code "122") (name "unconnected-(U$1B-IO_24-Pad117)") (class "Default")
      (node (ref "U$1") (pin "117") (pinfunction "IO_24_117") (pintype "bidirectional"))
    )
    (net (code "123") (name "unconnected-(U$1B-IO_25-Pad118)") (class "Default")
      (node (ref "U$1") (pin "118") (pinfunction "IO_25_118") (pintype "bidirectional"))
    )
    (net (code "124") (name "unconnected-(U$1B-IO_26-Pad119)") (class "Default")
      (node (ref "U$1") (pin "119") (pinfunction "IO_26_119") (pintype "bidirectional"))
    )
    (net (code "125") (name "unconnected-(U$1B-IO_27-Pad120)") (class "Default")
      (node (ref "U$1") (pin "120") (pinfunction "IO_27_120") (pintype "bidirectional"))
    )
    (net (code "126") (name "unconnected-(U$1B-IO_28-Pad121)") (class "Default")
      (node (ref "U$1") (pin "121") (pinfunction "IO_28_121") (pintype "bidirectional"))
    )
    (net (code "127") (name "unconnected-(U$1B-IO_29-Pad130)") (class "Default")
      (node (ref "U$1") (pin "130") (pinfunction "IO_29_130") (pintype "bidirectional"))
    )
    (net (code "128") (name "unconnected-(U$1B-IO_30-Pad131)") (class "Default")
      (node (ref "U$1") (pin "131") (pinfunction "IO_30_131") (pintype "bidirectional"))
    )
    (net (code "129") (name "unconnected-(U$1B-IO_31-Pad132)") (class "Default")
      (node (ref "U$1") (pin "132") (pinfunction "IO_31_132") (pintype "bidirectional"))
    )
    (net (code "130") (name "unconnected-(U$1B-IO_32-Pad133)") (class "Default")
      (node (ref "U$1") (pin "133") (pinfunction "IO_32_133") (pintype "bidirectional"))
    )
    (net (code "131") (name "unconnected-(U$1B-IO_33-Pad135)") (class "Default")
      (node (ref "U$1") (pin "135") (pinfunction "IO_33_135") (pintype "bidirectional"))
    )
    (net (code "132") (name "unconnected-(U$1B-IO_34-Pad136)") (class "Default")
      (node (ref "U$1") (pin "136") (pinfunction "IO_34_136") (pintype "bidirectional"))
    )
    (net (code "133") (name "unconnected-(U$1B-IO_35-Pad137)") (class "Default")
      (node (ref "U$1") (pin "137") (pinfunction "IO_35_137") (pintype "bidirectional"))
    )
    (net (code "134") (name "unconnected-(U$1B-IO_36-Pad138)") (class "Default")
      (node (ref "U$1") (pin "138") (pinfunction "IO_36_138") (pintype "bidirectional"))
    )
    (net (code "135") (name "unconnected-(U$1B-IO{slash}CS-Pad143)") (class "Default")
      (node (ref "U$1") (pin "143") (pinfunction "IO/CS_143") (pintype "bidirectional"))
    )
    (net (code "136") (name "unconnected-(U$1B-IO{slash}DATA1-Pad109)") (class "Default")
      (node (ref "U$1") (pin "109") (pinfunction "IO/DATA1_109") (pintype "bidirectional"))
    )
    (net (code "137") (name "unconnected-(U$1B-IO{slash}DATA2-Pad110)") (class "Default")
      (node (ref "U$1") (pin "110") (pinfunction "IO/DATA2_110") (pintype "bidirectional"))
    )
    (net (code "138") (name "unconnected-(U$1B-IO{slash}DATA3-Pad111)") (class "Default")
      (node (ref "U$1") (pin "111") (pinfunction "IO/DATA3_111") (pintype "bidirectional"))
    )
    (net (code "139") (name "unconnected-(U$1B-IO{slash}DATA4-Pad112)") (class "Default")
      (node (ref "U$1") (pin "112") (pinfunction "IO/DATA4_112") (pintype "bidirectional"))
    )
    (net (code "140") (name "unconnected-(U$1B-IO{slash}DATA5-Pad113)") (class "Default")
      (node (ref "U$1") (pin "113") (pinfunction "IO/DATA5_113") (pintype "bidirectional"))
    )
    (net (code "141") (name "unconnected-(U$1B-IO{slash}DATA6-Pad114)") (class "Default")
      (node (ref "U$1") (pin "114") (pinfunction "IO/DATA6_114") (pintype "bidirectional"))
    )
    (net (code "142") (name "unconnected-(U$1B-IO{slash}DATA7-Pad116)") (class "Default")
      (node (ref "U$1") (pin "116") (pinfunction "IO/DATA7_116") (pintype "bidirectional"))
    )
    (net (code "143") (name "unconnected-(U$1B-IO{slash}DEV_CLRN-Pad122)") (class "Default")
      (node (ref "U$1") (pin "122") (pinfunction "IO/DEV_CLRN_122") (pintype "bidirectional"))
    )
    (net (code "144") (name "unconnected-(U$1B-IO{slash}DEV_OE-Pad128)") (class "Default")
      (node (ref "U$1") (pin "128") (pinfunction "IO/DEV_OE_128") (pintype "bidirectional"))
    )
    (net (code "145") (name "unconnected-(U$1B-IO{slash}NCS-Pad144)") (class "Default")
      (node (ref "U$1") (pin "144") (pinfunction "IO/NCS_144") (pintype "bidirectional"))
    )
    (net (code "146") (name "unconnected-(U$1B-IO{slash}NRS-Pad141)") (class "Default")
      (node (ref "U$1") (pin "141") (pinfunction "IO/NRS_141") (pintype "bidirectional"))
    )
    (net (code "147") (name "unconnected-(U$1B-IO{slash}NWS-Pad142)") (class "Default")
      (node (ref "U$1") (pin "142") (pinfunction "IO/NWS_142") (pintype "bidirectional"))
    )
    (net (code "148") (name "unconnected-(U$1B-TDI-Pad105)") (class "Default")
      (node (ref "U$1") (pin "105") (pinfunction "TDI_105") (pintype "input"))
    )
  )
)
